# Logic_Board2.net
KiCad netlist of a schematic drawn in EAGLE
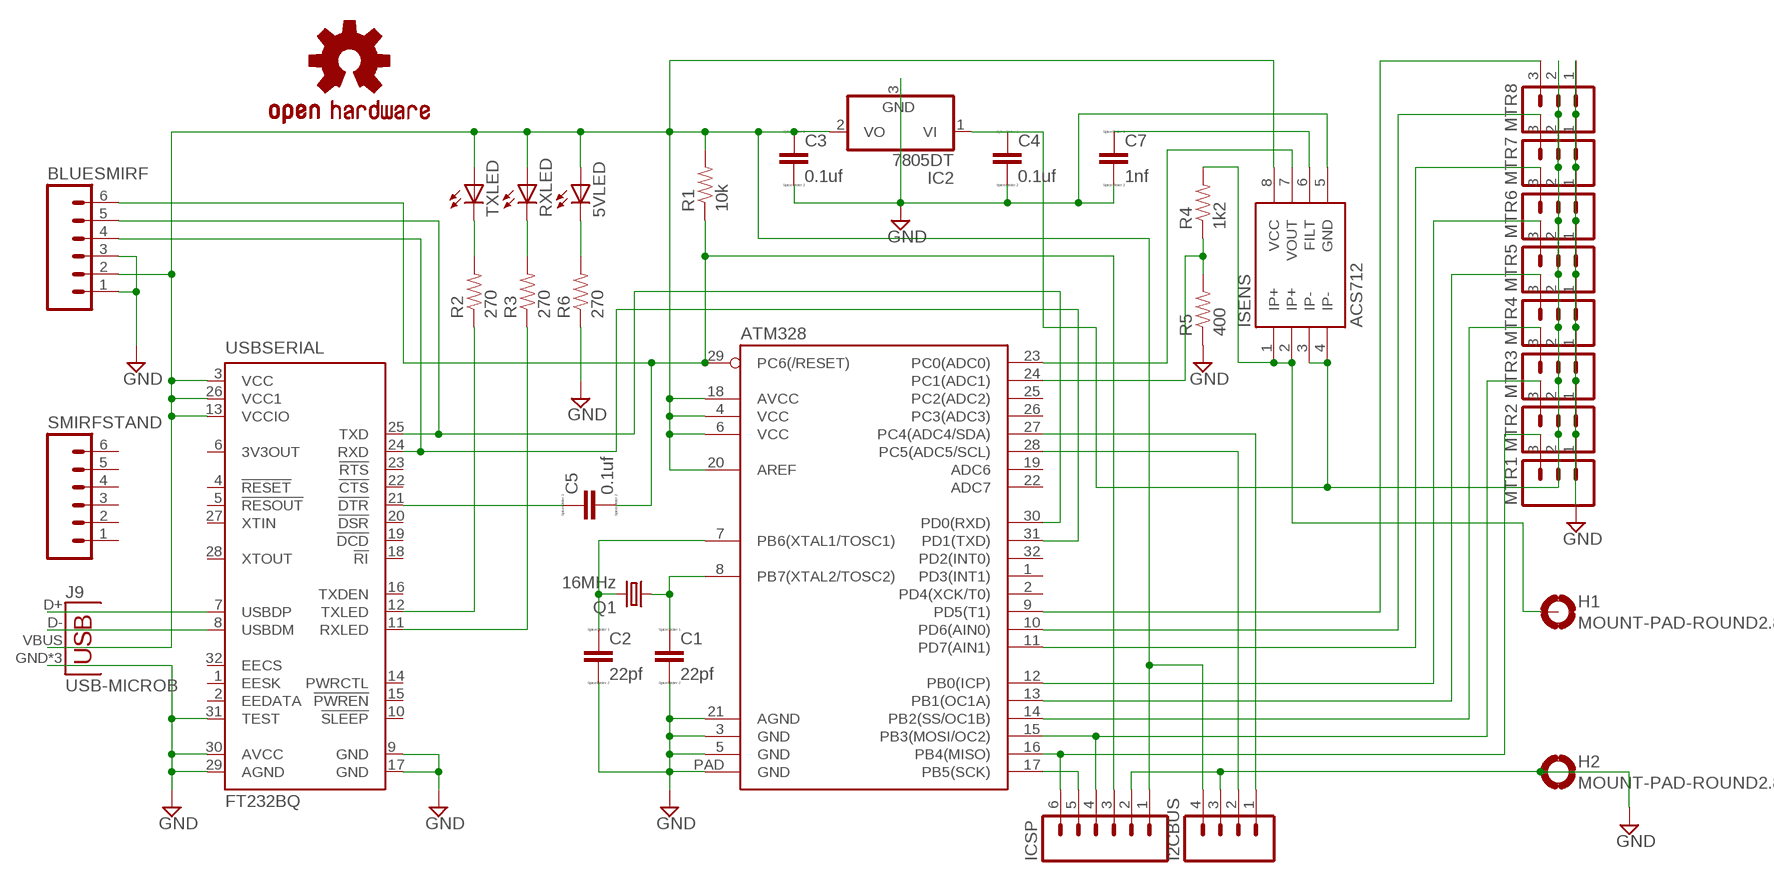
[diagram p0: schematic, sheet 1]

(export (version "E")
  (design (tool "Eeschema 10.0.6"))
  (components
    (comp (ref "5VLED")
      (value "LEDCHIPLED_0805")
      (footprint "eagle-import:CHIPLED_0805")
      (libsource (lib "eagle-import") (part "LEDCHIPLED_0805"))
    )
    (comp (ref "ATM328")
      (value "ATMEGA328P_MLFMLF32")
      (footprint "eagle-import:MLF32-PAD")
      (libsource (lib "eagle-import") (part "ATMEGA328P_MLFMLF32"))
    )
    (comp (ref "BLUESMIRF")
      (value "M06NO_SILK_YES_STOP")
      (footprint "eagle-import:1X06_NO_SILK_YES_STOP")
      (libsource (lib "eagle-import") (part "M06NO_SILK_YES_STOP"))
    )
    (comp (ref "C1")
      (value "22pf")
      (footprint "eagle-import:C0805")
      (libsource (lib "eagle-import") (part "C"))
    )
    (comp (ref "C2")
      (value "22pf")
      (footprint "eagle-import:C0805")
      (libsource (lib "eagle-import") (part "C"))
    )
    (comp (ref "C3")
      (value "0.1uf")
      (footprint "eagle-import:C0805")
      (libsource (lib "eagle-import") (part "C"))
    )
    (comp (ref "C4")
      (value "0.1uf")
      (footprint "eagle-import:C0805")
      (libsource (lib "eagle-import") (part "C"))
    )
    (comp (ref "C5")
      (value "0.1uf")
      (footprint "eagle-import:C0805")
      (libsource (lib "eagle-import") (part "C"))
    )
    (comp (ref "C7")
      (value "1nf")
      (footprint "eagle-import:C0805")
      (libsource (lib "eagle-import") (part "C"))
    )
    (comp (ref "H1")
      (value "MOUNT-PAD-ROUND2.8")
      (footprint "eagle-import:2,8-PAD")
      (libsource (lib "eagle-import") (part "MOUNT-PAD-ROUND2.8"))
    )
    (comp (ref "H2")
      (value "MOUNT-PAD-ROUND2.8")
      (footprint "eagle-import:2,8-PAD")
      (libsource (lib "eagle-import") (part "MOUNT-PAD-ROUND2.8"))
    )
    (comp (ref "I2CBUS")
      (value "M04NO_SILK_ALL_ROUND")
      (footprint "eagle-import:1X04_NO_SILK_ALL_ROUND")
      (libsource (lib "eagle-import") (part "M04NO_SILK_ALL_ROUND"))
    )
    (comp (ref "IC2")
      (value "7805DT")
      (footprint "eagle-import:TO252")
      (libsource (lib "eagle-import") (part "78DT05"))
    )
    (comp (ref "ICSP")
      (value "M06NO_SILK_YES_STOP")
      (footprint "eagle-import:1X06_NO_SILK_YES_STOP")
      (libsource (lib "eagle-import") (part "M06NO_SILK_YES_STOP"))
    )
    (comp (ref "ISENS")
      (value "ACS712")
      (footprint "eagle-import:SO08")
      (libsource (lib "eagle-import") (part "ACS712"))
    )
    (comp (ref "J9")
      (value "USB-MICROB")
      (footprint "eagle-import:USB-MICROB")
      (libsource (lib "eagle-import") (part "USB-MICROB"))
    )
    (comp (ref "LOGO1")
      (value "OSHW-LOGOM")
      (footprint "eagle-import:OSHW-LOGO-M")
      (libsource (lib "eagle-import") (part "OSHW-LOGOM"))
    )
    (comp (ref "MTR1")
      (value "M03PTH")
      (footprint "eagle-import:1X03")
      (libsource (lib "eagle-import") (part "M03PTH"))
    )
    (comp (ref "MTR2")
      (value "M03PTH")
      (footprint "eagle-import:1X03")
      (libsource (lib "eagle-import") (part "M03PTH"))
    )
    (comp (ref "MTR3")
      (value "M03PTH")
      (footprint "eagle-import:1X03")
      (libsource (lib "eagle-import") (part "M03PTH"))
    )
    (comp (ref "MTR4")
      (value "M03PTH")
      (footprint "eagle-import:1X03")
      (libsource (lib "eagle-import") (part "M03PTH"))
    )
    (comp (ref "MTR5")
      (value "M03PTH")
      (footprint "eagle-import:1X03")
      (libsource (lib "eagle-import") (part "M03PTH"))
    )
    (comp (ref "MTR6")
      (value "M03PTH")
      (footprint "eagle-import:1X03")
      (libsource (lib "eagle-import") (part "M03PTH"))
    )
    (comp (ref "MTR7")
      (value "M03PTH")
      (footprint "eagle-import:1X03")
      (libsource (lib "eagle-import") (part "M03PTH"))
    )
    (comp (ref "MTR8")
      (value "M03PTH")
      (footprint "eagle-import:1X03")
      (libsource (lib "eagle-import") (part "M03PTH"))
    )
    (comp (ref "Q1")
      (value "16MHz")
      (footprint "eagle-import:HC49U-V")
      (libsource (lib "eagle-import") (part "CRYSTALHC49U-V"))
    )
    (comp (ref "R1")
      (value "10k")
      (footprint "eagle-import:0805")
      (libsource (lib "eagle-import") (part "RESISTOR0805-RES"))
    )
    (comp (ref "R2")
      (value "270")
      (footprint "eagle-import:0805")
      (libsource (lib "eagle-import") (part "RESISTOR0805-RES"))
    )
    (comp (ref "R3")
      (value "270")
      (footprint "eagle-import:0805")
      (libsource (lib "eagle-import") (part "RESISTOR0805-RES"))
    )
    (comp (ref "R4")
      (value "1k2")
      (footprint "eagle-import:0805")
      (libsource (lib "eagle-import") (part "RESISTOR0805-RES"))
    )
    (comp (ref "R5")
      (value "400")
      (footprint "eagle-import:0805")
      (libsource (lib "eagle-import") (part "RESISTOR0805-RES"))
    )
    (comp (ref "R6")
      (value "270")
      (footprint "eagle-import:0805")
      (libsource (lib "eagle-import") (part "RESISTOR0805-RES"))
    )
    (comp (ref "RXLED")
      (value "LEDCHIPLED_0805")
      (footprint "eagle-import:CHIPLED_0805")
      (libsource (lib "eagle-import") (part "LEDCHIPLED_0805"))
    )
    (comp (ref "SMIRFSTAND")
      (value "M06NO_SILK_YES_STOP")
      (footprint "eagle-import:1X06_NO_SILK_YES_STOP")
      (libsource (lib "eagle-import") (part "M06NO_SILK_YES_STOP"))
    )
    (comp (ref "TXLED")
      (value "LEDCHIPLED_0805")
      (footprint "eagle-import:CHIPLED_0805")
      (libsource (lib "eagle-import") (part "LEDCHIPLED_0805"))
    )
    (comp (ref "USBSERIAL")
      (value "FT232BQ")
      (footprint "eagle-import:QFN32")
      (libsource (lib "eagle-import") (part "FT232BQ"))
    )
  )
  (nets
    (net (code "1") (name "GND") (class "Default")
      (node (ref "ATM328") (pin "21") (pinfunction "AGND_21") (pintype "bidirectional"))
      (node (ref "ATM328") (pin "3") (pinfunction "GND_3") (pintype "bidirectional"))
      (node (ref "ATM328") (pin "5") (pinfunction "GND_5") (pintype "bidirectional"))
      (node (ref "ATM328") (pin "PAD") (pinfunction "GND_PAD") (pintype "bidirectional"))
      (node (ref "BLUESMIRF") (pin "1") (pinfunction "1_1") (pintype "passive"))
      (node (ref "BLUESMIRF") (pin "3") (pinfunction "3_3") (pintype "passive"))
      (node (ref "C1") (pin "2") (pinfunction "2_2") (pintype "passive"))
      (node (ref "C2") (pin "2") (pinfunction "2_2") (pintype "passive"))
      (node (ref "C3") (pin "2") (pinfunction "2_2") (pintype "passive"))
      (node (ref "C4") (pin "2") (pinfunction "2_2") (pintype "passive"))
      (node (ref "C7") (pin "2") (pinfunction "2_2") (pintype "passive"))
      (node (ref "H2") (pin "B2,8") (pinfunction "MOUNT_B2,8") (pintype "passive"))
      (node (ref "I2CBUS") (pin "3") (pinfunction "3_3") (pintype "passive"))
      (node (ref "IC2") (pin "3") (pinfunction "GND_3") (pintype "passive"))
      (node (ref "ICSP") (pin "2") (pinfunction "2_2") (pintype "passive"))
      (node (ref "ISENS") (pin "5") (pinfunction "GND_5") (pintype "bidirectional"))
      (node (ref "J9") (pin "GND") (pinfunction "GND_GND") (pintype "bidirectional"))
      (node (ref "J9") (pin "MT1") (pinfunction "GND_MT1") (pintype "bidirectional"))
      (node (ref "J9") (pin "MT2") (pinfunction "GND_MT2") (pintype "bidirectional"))
      (node (ref "MTR1") (pin "1") (pinfunction "1_1") (pintype "passive"))
      (node (ref "MTR2") (pin "1") (pinfunction "1_1") (pintype "passive"))
      (node (ref "MTR3") (pin "1") (pinfunction "1_1") (pintype "passive"))
      (node (ref "MTR4") (pin "1") (pinfunction "1_1") (pintype "passive"))
      (node (ref "MTR5") (pin "1") (pinfunction "1_1") (pintype "passive"))
      (node (ref "MTR6") (pin "1") (pinfunction "1_1") (pintype "passive"))
      (node (ref "MTR7") (pin "1") (pinfunction "1_1") (pintype "passive"))
      (node (ref "MTR8") (pin "1") (pinfunction "1_1") (pintype "passive"))
      (node (ref "R5") (pin "1") (pinfunction "1_1") (pintype "passive"))
      (node (ref "R6") (pin "1") (pinfunction "1_1") (pintype "passive"))
      (node (ref "USBSERIAL") (pin "17") (pinfunction "GND_17") (pintype "power_in"))
      (node (ref "USBSERIAL") (pin "29") (pinfunction "AGND_29") (pintype "power_in"))
      (node (ref "USBSERIAL") (pin "30") (pinfunction "AVCC_30") (pintype "power_in"))
      (node (ref "USBSERIAL") (pin "31") (pinfunction "TEST_31") (pintype "input"))
      (node (ref "USBSERIAL") (pin "9") (pinfunction "GND_9") (pintype "power_in"))
    )
    (net (code "2") (name "Net-(5VLED-PadC)") (class "Default")
      (node (ref "5VLED") (pin "C") (pinfunction "C_C") (pintype "passive"))
      (node (ref "R6") (pin "2") (pinfunction "2_2") (pintype "passive"))
    )
    (net (code "3") (name "Net-(ATM328-AREF)") (class "Default")
      (node (ref "5VLED") (pin "A") (pinfunction "A_A") (pintype "passive"))
      (node (ref "ATM328") (pin "18") (pinfunction "AVCC_18") (pintype "bidirectional"))
      (node (ref "ATM328") (pin "20") (pinfunction "AREF_20") (pintype "bidirectional"))
      (node (ref "ATM328") (pin "4") (pinfunction "VCC_4") (pintype "bidirectional"))
      (node (ref "ATM328") (pin "6") (pinfunction "VCC_6") (pintype "bidirectional"))
      (node (ref "BLUESMIRF") (pin "2") (pinfunction "2_2") (pintype "passive"))
      (node (ref "C3") (pin "1") (pinfunction "1_1") (pintype "passive"))
      (node (ref "I2CBUS") (pin "4") (pinfunction "4_4") (pintype "passive"))
      (node (ref "IC2") (pin "2") (pinfunction "VO_2") (pintype "passive"))
      (node (ref "ICSP") (pin "1") (pinfunction "1_1") (pintype "passive"))
      (node (ref "ISENS") (pin "8") (pinfunction "VCC_8") (pintype "bidirectional"))
      (node (ref "J9") (pin "VBUS") (pinfunction "VBUS_VBUS") (pintype "bidirectional"))
      (node (ref "R1") (pin "2") (pinfunction "2_2") (pintype "passive"))
      (node (ref "RXLED") (pin "A") (pinfunction "A_A") (pintype "passive"))
      (node (ref "TXLED") (pin "A") (pinfunction "A_A") (pintype "passive"))
      (node (ref "USBSERIAL") (pin "13") (pinfunction "VCCIO_13") (pintype "power_in"))
      (node (ref "USBSERIAL") (pin "26") (pinfunction "VCC1_26") (pintype "power_in"))
      (node (ref "USBSERIAL") (pin "3") (pinfunction "VCC_3") (pintype "power_in"))
    )
    (net (code "4") (name "Net-(ATM328-PB0(ICP))") (class "Default")
      (node (ref "ATM328") (pin "12") (pinfunction "PB0(ICP)_12") (pintype "bidirectional"))
      (node (ref "MTR5") (pin "3") (pinfunction "3_3") (pintype "passive"))
    )
    (net (code "5") (name "Net-(ATM328-PB1(OC1A))") (class "Default")
      (node (ref "ATM328") (pin "13") (pinfunction "PB1(OC1A)_13") (pintype "bidirectional"))
      (node (ref "MTR4") (pin "3") (pinfunction "3_3") (pintype "passive"))
    )
    (net (code "6") (name "Net-(ATM328-PB2(SS{slash}OC1B))") (class "Default")
      (node (ref "ATM328") (pin "14") (pinfunction "PB2(SS/OC1B)_14") (pintype "bidirectional"))
      (node (ref "MTR3") (pin "3") (pinfunction "3_3") (pintype "passive"))
    )
    (net (code "7") (name "Net-(ATM328-PB3(MOSI{slash}OC2))") (class "Default")
      (node (ref "ATM328") (pin "15") (pinfunction "PB3(MOSI/OC2)_15") (pintype "bidirectional"))
      (node (ref "ICSP") (pin "4") (pinfunction "4_4") (pintype "passive"))
      (node (ref "MTR2") (pin "3") (pinfunction "3_3") (pintype "passive"))
    )
    (net (code "8") (name "Net-(ATM328-PB4(MISO))") (class "Default")
      (node (ref "ATM328") (pin "16") (pinfunction "PB4(MISO)_16") (pintype "bidirectional"))
      (node (ref "ICSP") (pin "6") (pinfunction "6_6") (pintype "passive"))
      (node (ref "MTR1") (pin "3") (pinfunction "3_3") (pintype "passive"))
    )
    (net (code "9") (name "Net-(ATM328-PB5(SCK))") (class "Default")
      (node (ref "ATM328") (pin "17") (pinfunction "PB5(SCK)_17") (pintype "bidirectional"))
      (node (ref "ICSP") (pin "5") (pinfunction "5_5") (pintype "passive"))
    )
    (net (code "10") (name "Net-(ATM328-PB6(XTAL1{slash}TOSC1))") (class "Default")
      (node (ref "ATM328") (pin "7") (pinfunction "PB6(XTAL1/TOSC1)_7") (pintype "bidirectional"))
      (node (ref "C2") (pin "1") (pinfunction "1_1") (pintype "passive"))
      (node (ref "Q1") (pin "2") (pinfunction "2_2") (pintype "passive"))
    )
    (net (code "11") (name "Net-(ATM328-PB7(XTAL2{slash}TOSC2))") (class "Default")
      (node (ref "ATM328") (pin "8") (pinfunction "PB7(XTAL2/TOSC2)_8") (pintype "bidirectional"))
      (node (ref "C1") (pin "1") (pinfunction "1_1") (pintype "passive"))
      (node (ref "Q1") (pin "1") (pinfunction "1_1") (pintype "passive"))
    )
    (net (code "12") (name "Net-(ATM328-PC0(ADC0))") (class "Default")
      (node (ref "ATM328") (pin "23") (pinfunction "PC0(ADC0)_23") (pintype "bidirectional"))
      (node (ref "ISENS") (pin "7") (pinfunction "VOUT_7") (pintype "bidirectional"))
    )
    (net (code "13") (name "Net-(ATM328-PC1(ADC1))") (class "Default")
      (node (ref "ATM328") (pin "24") (pinfunction "PC1(ADC1)_24") (pintype "bidirectional"))
      (node (ref "R4") (pin "1") (pinfunction "1_1") (pintype "passive"))
      (node (ref "R5") (pin "2") (pinfunction "2_2") (pintype "passive"))
    )
    (net (code "14") (name "Net-(ATM328-PC4(ADC4{slash}SDA))") (class "Default")
      (node (ref "ATM328") (pin "27") (pinfunction "PC4(ADC4/SDA)_27") (pintype "bidirectional"))
      (node (ref "I2CBUS") (pin "1") (pinfunction "1_1") (pintype "passive"))
    )
    (net (code "15") (name "Net-(ATM328-PC5(ADC5{slash}SCL))") (class "Default")
      (node (ref "ATM328") (pin "28") (pinfunction "PC5(ADC5/SCL)_28") (pintype "bidirectional"))
      (node (ref "I2CBUS") (pin "2") (pinfunction "2_2") (pintype "passive"))
    )
    (net (code "16") (name "Net-(ATM328-PC6({slash}RESET))") (class "Default")
      (node (ref "ATM328") (pin "29") (pinfunction "PC6(/RESET)_29") (pintype "bidirectional"))
      (node (ref "BLUESMIRF") (pin "6") (pinfunction "6_6") (pintype "passive"))
      (node (ref "C5") (pin "2") (pinfunction "2_2") (pintype "passive"))
      (node (ref "ICSP") (pin "3") (pinfunction "3_3") (pintype "passive"))
      (node (ref "R1") (pin "1") (pinfunction "1_1") (pintype "passive"))
    )
    (net (code "17") (name "Net-(ATM328-PD0(RXD))") (class "Default")
      (node (ref "ATM328") (pin "30") (pinfunction "PD0(RXD)_30") (pintype "bidirectional"))
      (node (ref "BLUESMIRF") (pin "5") (pinfunction "5_5") (pintype "passive"))
      (node (ref "USBSERIAL") (pin "25") (pinfunction "TXD_25") (pintype "output"))
    )
    (net (code "18") (name "Net-(ATM328-PD1(TXD))") (class "Default")
      (node (ref "ATM328") (pin "31") (pinfunction "PD1(TXD)_31") (pintype "bidirectional"))
      (node (ref "BLUESMIRF") (pin "4") (pinfunction "4_4") (pintype "passive"))
      (node (ref "USBSERIAL") (pin "24") (pinfunction "RXD_24") (pintype "input"))
    )
    (net (code "19") (name "Net-(ATM328-PD5(T1))") (class "Default")
      (node (ref "ATM328") (pin "9") (pinfunction "PD5(T1)_9") (pintype "bidirectional"))
      (node (ref "MTR8") (pin "3") (pinfunction "3_3") (pintype "passive"))
    )
    (net (code "20") (name "Net-(ATM328-PD6(AIN0))") (class "Default")
      (node (ref "ATM328") (pin "10") (pinfunction "PD6(AIN0)_10") (pintype "bidirectional"))
      (node (ref "MTR7") (pin "3") (pinfunction "3_3") (pintype "passive"))
    )
    (net (code "21") (name "Net-(ATM328-PD7(AIN1))") (class "Default")
      (node (ref "ATM328") (pin "11") (pinfunction "PD7(AIN1)_11") (pintype "bidirectional"))
      (node (ref "MTR6") (pin "3") (pinfunction "3_3") (pintype "passive"))
    )
    (net (code "22") (name "Net-(H1-MOUNT)") (class "Default")
      (node (ref "H1") (pin "B2,8") (pinfunction "MOUNT_B2,8") (pintype "passive"))
      (node (ref "ISENS") (pin "1") (pinfunction "IP+_1") (pintype "bidirectional"))
      (node (ref "ISENS") (pin "2") (pinfunction "IP+_2") (pintype "bidirectional"))
      (node (ref "R4") (pin "2") (pinfunction "2_2") (pintype "passive"))
    )
    (net (code "23") (name "Net-(IC2-VI)") (class "Default")
      (node (ref "C4") (pin "1") (pinfunction "1_1") (pintype "passive"))
      (node (ref "IC2") (pin "1") (pinfunction "VI_1") (pintype "input"))
      (node (ref "ISENS") (pin "3") (pinfunction "IP-_3") (pintype "bidirectional"))
      (node (ref "ISENS") (pin "4") (pinfunction "IP-_4") (pintype "bidirectional"))
      (node (ref "MTR1") (pin "2") (pinfunction "2_2") (pintype "passive"))
      (node (ref "MTR2") (pin "2") (pinfunction "2_2") (pintype "passive"))
      (node (ref "MTR3") (pin "2") (pinfunction "2_2") (pintype "passive"))
      (node (ref "MTR4") (pin "2") (pinfunction "2_2") (pintype "passive"))
      (node (ref "MTR5") (pin "2") (pinfunction "2_2") (pintype "passive"))
      (node (ref "MTR6") (pin "2") (pinfunction "2_2") (pintype "passive"))
      (node (ref "MTR7") (pin "2") (pinfunction "2_2") (pintype "passive"))
      (node (ref "MTR8") (pin "2") (pinfunction "2_2") (pintype "passive"))
    )
    (net (code "24") (name "Net-(ISENS-FILT)") (class "Default")
      (node (ref "C7") (pin "1") (pinfunction "1_1") (pintype "passive"))
      (node (ref "ISENS") (pin "6") (pinfunction "FILT_6") (pintype "bidirectional"))
    )
    (net (code "25") (name "Net-(R2-Pad2)") (class "Default")
      (node (ref "R2") (pin "2") (pinfunction "2_2") (pintype "passive"))
      (node (ref "TXLED") (pin "C") (pinfunction "C_C") (pintype "passive"))
    )
    (net (code "26") (name "Net-(R3-Pad2)") (class "Default")
      (node (ref "R3") (pin "2") (pinfunction "2_2") (pintype "passive"))
      (node (ref "RXLED") (pin "C") (pinfunction "C_C") (pintype "passive"))
    )
    (net (code "27") (name "Net-(USBSERIAL-RXLED)") (class "Default")
      (node (ref "R3") (pin "1") (pinfunction "1_1") (pintype "passive"))
      (node (ref "USBSERIAL") (pin "11") (pinfunction "RXLED_11") (pintype "bidirectional"))
    )
    (net (code "28") (name "Net-(USBSERIAL-TXLED)") (class "Default")
      (node (ref "R2") (pin "1") (pinfunction "1_1") (pintype "passive"))
      (node (ref "USBSERIAL") (pin "12") (pinfunction "TXLED_12") (pintype "bidirectional"))
    )
    (net (code "29") (name "Net-(USBSERIAL-USBDM)") (class "Default")
      (node (ref "J9") (pin "D-") (pinfunction "D-_D-") (pintype "bidirectional"))
      (node (ref "USBSERIAL") (pin "8") (pinfunction "USBDM_8") (pintype "bidirectional"))
    )
    (net (code "30") (name "Net-(USBSERIAL-USBDP)") (class "Default")
      (node (ref "J9") (pin "D+") (pinfunction "D+_D+") (pintype "bidirectional"))
      (node (ref "USBSERIAL") (pin "7") (pinfunction "USBDP_7") (pintype "bidirectional"))
    )
    (net (code "31") (name "Net-(USBSERIAL-~{DTR})") (class "Default")
      (node (ref "C5") (pin "1") (pinfunction "1_1") (pintype "passive"))
      (node (ref "USBSERIAL") (pin "21") (pinfunction "~{DTR}_21") (pintype "output"))
    )
    (net (code "32") (name "unconnected-(ATM328-ADC6-Pad19)") (class "Default")
      (node (ref "ATM328") (pin "19") (pinfunction "ADC6_19") (pintype "bidirectional"))
    )
    (net (code "33") (name "unconnected-(ATM328-ADC7-Pad22)") (class "Default")
      (node (ref "ATM328") (pin "22") (pinfunction "ADC7_22") (pintype "bidirectional"))
    )
    (net (code "34") (name "unconnected-(ATM328-PC2(ADC2)-Pad25)") (class "Default")
      (node (ref "ATM328") (pin "25") (pinfunction "PC2(ADC2)_25") (pintype "bidirectional"))
    )
    (net (code "35") (name "unconnected-(ATM328-PC3(ADC3)-Pad26)") (class "Default")
      (node (ref "ATM328") (pin "26") (pinfunction "PC3(ADC3)_26") (pintype "bidirectional"))
    )
    (net (code "36") (name "unconnected-(ATM328-PD2(INT0)-Pad32)") (class "Default")
      (node (ref "ATM328") (pin "32") (pinfunction "PD2(INT0)_32") (pintype "bidirectional"))
    )
    (net (code "37") (name "unconnected-(ATM328-PD3(INT1)-Pad1)") (class "Default")
      (node (ref "ATM328") (pin "1") (pinfunction "PD3(INT1)_1") (pintype "bidirectional"))
    )
    (net (code "38") (name "unconnected-(ATM328-PD4(XCK{slash}T0)-Pad2)") (class "Default")
      (node (ref "ATM328") (pin "2") (pinfunction "PD4(XCK/T0)_2") (pintype "bidirectional"))
    )
    (net (code "39") (name "unconnected-(SMIRFSTAND-Pad1)") (class "Default")
      (node (ref "SMIRFSTAND") (pin "1") (pinfunction "1_1") (pintype "passive"))
    )
    (net (code "40") (name "unconnected-(SMIRFSTAND-Pad2)") (class "Default")
      (node (ref "SMIRFSTAND") (pin "2") (pinfunction "2_2") (pintype "passive"))
    )
    (net (code "41") (name "unconnected-(SMIRFSTAND-Pad3)") (class "Default")
      (node (ref "SMIRFSTAND") (pin "3") (pinfunction "3_3") (pintype "passive"))
    )
    (net (code "42") (name "unconnected-(SMIRFSTAND-Pad4)") (class "Default")
      (node (ref "SMIRFSTAND") (pin "4") (pinfunction "4_4") (pintype "passive"))
    )
    (net (code "43") (name "unconnected-(SMIRFSTAND-Pad5)") (class "Default")
      (node (ref "SMIRFSTAND") (pin "5") (pinfunction "5_5") (pintype "passive"))
    )
    (net (code "44") (name "unconnected-(SMIRFSTAND-Pad6)") (class "Default")
      (node (ref "SMIRFSTAND") (pin "6") (pinfunction "6_6") (pintype "passive"))
    )
    (net (code "45") (name "unconnected-(USBSERIAL-3V3OUT-Pad6)") (class "Default")
      (node (ref "USBSERIAL") (pin "6") (pinfunction "3V3OUT_6") (pintype "output"))
    )
    (net (code "46") (name "unconnected-(USBSERIAL-EECS-Pad32)") (class "Default")
      (node (ref "USBSERIAL") (pin "32") (pinfunction "EECS_32") (pintype "input"))
    )
    (net (code "47") (name "unconnected-(USBSERIAL-EEDATA-Pad2)") (class "Default")
      (node (ref "USBSERIAL") (pin "2") (pinfunction "EEDATA_2") (pintype "input"))
    )
    (net (code "48") (name "unconnected-(USBSERIAL-EESK-Pad1)") (class "Default")
      (node (ref "USBSERIAL") (pin "1") (pinfunction "EESK_1") (pintype "input"))
    )
    (net (code "49") (name "unconnected-(USBSERIAL-PWRCTL-Pad14)") (class "Default")
      (node (ref "USBSERIAL") (pin "14") (pinfunction "PWRCTL_14") (pintype "bidirectional"))
    )
    (net (code "50") (name "unconnected-(USBSERIAL-TXDEN-Pad16)") (class "Default")
      (node (ref "USBSERIAL") (pin "16") (pinfunction "TXDEN_16") (pintype "bidirectional"))
    )
    (net (code "51") (name "unconnected-(USBSERIAL-XTIN-Pad27)") (class "Default")
      (node (ref "USBSERIAL") (pin "27") (pinfunction "XTIN_27") (pintype "input"))
    )
    (net (code "52") (name "unconnected-(USBSERIAL-XTOUT-Pad28)") (class "Default")
      (node (ref "USBSERIAL") (pin "28") (pinfunction "XTOUT_28") (pintype "output"))
    )
    (net (code "53") (name "unconnected-(USBSERIAL-~{CTS}-Pad22)") (class "Default")
      (node (ref "USBSERIAL") (pin "22") (pinfunction "~{CTS}_22") (pintype "input"))
    )
    (net (code "54") (name "unconnected-(USBSERIAL-~{DCD}-Pad19)") (class "Default")
      (node (ref "USBSERIAL") (pin "19") (pinfunction "~{DCD}_19") (pintype "input"))
    )
    (net (code "55") (name "unconnected-(USBSERIAL-~{DSR}-Pad20)") (class "Default")
      (node (ref "USBSERIAL") (pin "20") (pinfunction "~{DSR}_20") (pintype "input"))
    )
    (net (code "56") (name "unconnected-(USBSERIAL-~{PWREN}-Pad15)") (class "Default")
      (node (ref "USBSERIAL") (pin "15") (pinfunction "~{PWREN}_15") (pintype "bidirectional"))
    )
    (net (code "57") (name "unconnected-(USBSERIAL-~{RESET}-Pad4)") (class "Default")
      (node (ref "USBSERIAL") (pin "4") (pinfunction "~{RESET}_4") (pintype "input"))
    )
    (net (code "58") (name "unconnected-(USBSERIAL-~{RESOUT}-Pad5)") (class "Default")
      (node (ref "USBSERIAL") (pin "5") (pinfunction "~{RESOUT}_5") (pintype "input"))
    )
    (net (code "59") (name "unconnected-(USBSERIAL-~{RI}-Pad18)") (class "Default")
      (node (ref "USBSERIAL") (pin "18") (pinfunction "~{RI}_18") (pintype "input"))
    )
    (net (code "60") (name "unconnected-(USBSERIAL-~{RTS}-Pad23)") (class "Default")
      (node (ref "USBSERIAL") (pin "23") (pinfunction "~{RTS}_23") (pintype "output"))
    )
    (net (code "61") (name "unconnected-(USBSERIAL-~{SLEEP}-Pad10)") (class "Default")
      (node (ref "USBSERIAL") (pin "10") (pinfunction "~{SLEEP}_10") (pintype "input"))
    )
  )
)
